# Fensterkontakt5.net
KiCad netlist of a schematic drawn in EAGLE
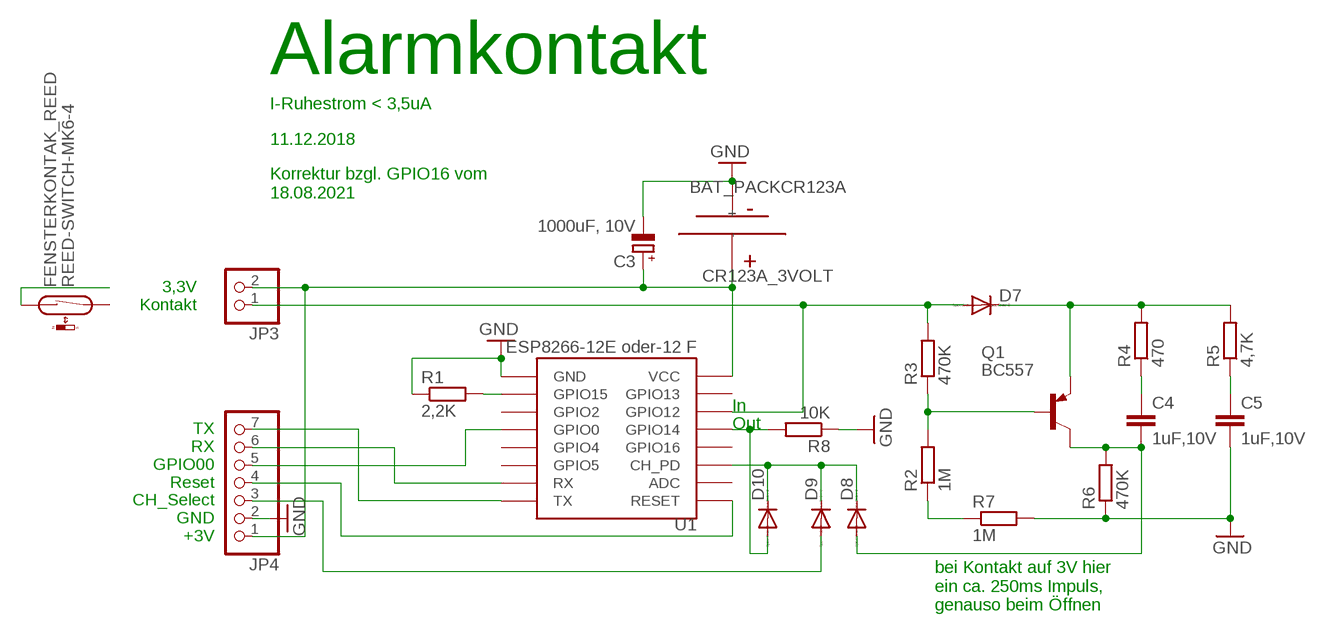
[diagram p0: schematic, sheet 1]

(export (version "E")
  (design (tool "Eeschema 10.0.6"))
  (components
    (comp (ref "C3")
      (value "1000uF, 10V")
      (footprint "eagle-import:E5-4")
      (libsource (lib "eagle-import") (part "CPOL-EUE5-4"))
    )
    (comp (ref "C4")
      (value "1uF,10V")
      (footprint "eagle-import:C075-032X103")
      (libsource (lib "eagle-import") (part "C-EU075-032X103"))
    )
    (comp (ref "C5")
      (value "1uF,10V")
      (footprint "eagle-import:C075-032X103")
      (libsource (lib "eagle-import") (part "C-EU075-032X103"))
    )
    (comp (ref "CR123A_3VOLT")
      (value "BAT_PACKCR123A")
      (footprint "eagle-import:BH123A")
      (fields (field (name "MANUFACTURER") "MPD") (field (name "MPN") "BH123A"))
      (libsource (lib "eagle-import") (part "BAT_PACKCR123A"))
    )
    (comp (ref "D7")
      (value "DIODE-D-7.5")
      (footprint "eagle-import:D-7.5")
      (libsource (lib "eagle-import") (part "DIODE-D-7.5"))
    )
    (comp (ref "D8")
      (value "DIODE-D-7.5")
      (footprint "eagle-import:D-7.5")
      (libsource (lib "eagle-import") (part "DIODE-D-7.5"))
    )
    (comp (ref "D9")
      (value "DIODE-D-7.5")
      (footprint "eagle-import:D-7.5")
      (libsource (lib "eagle-import") (part "DIODE-D-7.5"))
    )
    (comp (ref "D10")
      (value "DIODE-D-7.5")
      (footprint "eagle-import:D-7.5")
      (libsource (lib "eagle-import") (part "DIODE-D-7.5"))
    )
    (comp (ref "FENSTERKONTAK_REED")
      (value "REED-SWITCH-MK6-4")
      (footprint "eagle-import:MK6-4")
      (libsource (lib "eagle-import") (part "REED-SWITCH-MK6-4"))
    )
    (comp (ref "JP3")
      (value "PINHD-1X2")
      (footprint "eagle-import:1X02")
      (libsource (lib "eagle-import") (part "PINHD-1X2"))
    )
    (comp (ref "JP4")
      (value "PINHD-1X7")
      (footprint "eagle-import:1X07")
      (libsource (lib "eagle-import") (part "PINHD-1X7"))
    )
    (comp (ref "Q1")
      (value "BC557")
      (footprint "eagle-import:TO92-EBC")
      (libsource (lib "eagle-import") (part "BC557"))
    )
    (comp (ref "R1")
      (value "2,2K")
      (footprint "eagle-import:0207_7")
      (libsource (lib "eagle-import") (part "R-EU_0207/7"))
    )
    (comp (ref "R2")
      (value "1M")
      (footprint "eagle-import:0207_7")
      (libsource (lib "eagle-import") (part "R-EU_0207/7"))
    )
    (comp (ref "R3")
      (value "470K")
      (footprint "eagle-import:0207_7")
      (libsource (lib "eagle-import") (part "R-EU_0207/7"))
    )
    (comp (ref "R4")
      (value "470")
      (footprint "eagle-import:0207_7")
      (libsource (lib "eagle-import") (part "R-EU_0207/7"))
    )
    (comp (ref "R5")
      (value "4,7K")
      (footprint "eagle-import:0207_7")
      (libsource (lib "eagle-import") (part "R-EU_0207/7"))
    )
    (comp (ref "R6")
      (value "470K")
      (footprint "eagle-import:0207_7")
      (libsource (lib "eagle-import") (part "R-EU_0207/7"))
    )
    (comp (ref "R7")
      (value "1M")
      (footprint "eagle-import:0207_7")
      (libsource (lib "eagle-import") (part "R-EU_0207/7"))
    )
    (comp (ref "R8")
      (value "10K")
      (footprint "eagle-import:0207_7")
      (libsource (lib "eagle-import") (part "R-EU_0207/7"))
    )
    (comp (ref "U1")
      (value "ESP8266-12E oder-12 F")
      (footprint "eagle-import:ESP12")
      (libsource (lib "eagle-import") (part "ESP12"))
    )
  )
  (nets
    (net (code "1") (name "GND") (class "Default")
      (node (ref "C3") (pin "-") (pinfunction "-_-") (pintype "passive"))
      (node (ref "C5") (pin "2") (pinfunction "2_2") (pintype "passive"))
      (node (ref "CR123A_3VOLT") (pin "-") (pinfunction "-_-") (pintype "bidirectional"))
      (node (ref "JP4") (pin "2") (pinfunction "2_2") (pintype "passive"))
      (node (ref "R1") (pin "1") (pinfunction "1_1") (pintype "passive"))
      (node (ref "R6") (pin "1") (pinfunction "1_1") (pintype "passive"))
      (node (ref "R7") (pin "2") (pinfunction "2_2") (pintype "passive"))
      (node (ref "R8") (pin "1") (pinfunction "1_1") (pintype "passive"))
      (node (ref "U1") (pin "GND") (pinfunction "GND_GND") (pintype "bidirectional"))
    )
    (net (code "2") (name "Net-(C3-Pad+)") (class "Default")
      (node (ref "C3") (pin "+") (pinfunction "+_+") (pintype "passive"))
      (node (ref "CR123A_3VOLT") (pin "+") (pinfunction "+_+") (pintype "bidirectional"))
      (node (ref "JP3") (pin "2") (pinfunction "2_2") (pintype "passive"))
      (node (ref "JP4") (pin "1") (pinfunction "1_1") (pintype "passive"))
      (node (ref "U1") (pin "VCC") (pinfunction "VCC_VCC") (pintype "bidirectional"))
    )
    (net (code "3") (name "Net-(C4-Pad1)") (class "Default")
      (node (ref "C4") (pin "1") (pinfunction "1_1") (pintype "passive"))
      (node (ref "R4") (pin "1") (pinfunction "1_1") (pintype "passive"))
    )
    (net (code "4") (name "Net-(C4-Pad2)") (class "Default")
      (node (ref "C4") (pin "2") (pinfunction "2_2") (pintype "passive"))
      (node (ref "D8") (pin "A") (pinfunction "A_A") (pintype "passive"))
      (node (ref "Q1") (pin "C") (pinfunction "C_C") (pintype "passive"))
      (node (ref "R6") (pin "2") (pinfunction "2_2") (pintype "passive"))
    )
    (net (code "5") (name "Net-(C5-Pad1)") (class "Default")
      (node (ref "C5") (pin "1") (pinfunction "1_1") (pintype "passive"))
      (node (ref "R5") (pin "1") (pinfunction "1_1") (pintype "passive"))
    )
    (net (code "6") (name "Net-(D7-PadA)") (class "Default")
      (node (ref "D7") (pin "A") (pinfunction "A_A") (pintype "passive"))
      (node (ref "JP3") (pin "1") (pinfunction "1_1") (pintype "passive"))
      (node (ref "R3") (pin "2") (pinfunction "2_2") (pintype "passive"))
      (node (ref "U1") (pin "GPIO12") (pinfunction "GPIO12_GPIO12") (pintype "bidirectional"))
    )
    (net (code "7") (name "Net-(D7-PadC)") (class "Default")
      (node (ref "D7") (pin "C") (pinfunction "C_C") (pintype "passive"))
      (node (ref "Q1") (pin "E") (pinfunction "E_E") (pintype "passive"))
      (node (ref "R4") (pin "2") (pinfunction "2_2") (pintype "passive"))
      (node (ref "R5") (pin "2") (pinfunction "2_2") (pintype "passive"))
    )
    (net (code "8") (name "Net-(D9-PadA)") (class "Default")
      (node (ref "D9") (pin "A") (pinfunction "A_A") (pintype "passive"))
      (node (ref "JP4") (pin "3") (pinfunction "3_3") (pintype "passive"))
    )
    (net (code "9") (name "Net-(D10-PadA)") (class "Default")
      (node (ref "D10") (pin "A") (pinfunction "A_A") (pintype "passive"))
      (node (ref "R8") (pin "2") (pinfunction "2_2") (pintype "passive"))
      (node (ref "U1") (pin "GPIO14") (pinfunction "GPIO14_GPIO14") (pintype "bidirectional"))
    )
    (net (code "10") (name "Net-(D10-PadC)") (class "Default")
      (node (ref "D10") (pin "C") (pinfunction "C_C") (pintype "passive"))
      (node (ref "D8") (pin "C") (pinfunction "C_C") (pintype "passive"))
      (node (ref "D9") (pin "C") (pinfunction "C_C") (pintype "passive"))
      (node (ref "U1") (pin "CH_PD") (pinfunction "CH_PD_CH_PD") (pintype "bidirectional"))
    )
    (net (code "11") (name "Net-(JP4-Pad4)") (class "Default")
      (node (ref "JP4") (pin "4") (pinfunction "4_4") (pintype "passive"))
      (node (ref "U1") (pin "RESET") (pinfunction "RESET_RESET") (pintype "bidirectional"))
    )
    (net (code "12") (name "Net-(JP4-Pad5)") (class "Default")
      (node (ref "JP4") (pin "5") (pinfunction "5_5") (pintype "passive"))
      (node (ref "U1") (pin "GPIO0") (pinfunction "GPIO0_GPIO0") (pintype "bidirectional"))
    )
    (net (code "13") (name "Net-(JP4-Pad6)") (class "Default")
      (node (ref "JP4") (pin "6") (pinfunction "6_6") (pintype "passive"))
      (node (ref "U1") (pin "RX") (pinfunction "RX_RX") (pintype "bidirectional"))
    )
    (net (code "14") (name "Net-(JP4-Pad7)") (class "Default")
      (node (ref "JP4") (pin "7") (pinfunction "7_7") (pintype "passive"))
      (node (ref "U1") (pin "TX") (pinfunction "TX_TX") (pintype "bidirectional"))
    )
    (net (code "15") (name "Net-(Q1-PadB)") (class "Default")
      (node (ref "Q1") (pin "B") (pinfunction "B_B") (pintype "passive"))
      (node (ref "R2") (pin "2") (pinfunction "2_2") (pintype "passive"))
      (node (ref "R3") (pin "1") (pinfunction "1_1") (pintype "passive"))
    )
    (net (code "16") (name "Net-(R1-Pad2)") (class "Default")
      (node (ref "R1") (pin "2") (pinfunction "2_2") (pintype "passive"))
      (node (ref "U1") (pin "GPIO15") (pinfunction "GPIO15_GPIO15") (pintype "bidirectional"))
    )
    (net (code "17") (name "Net-(R2-Pad1)") (class "Default")
      (node (ref "R2") (pin "1") (pinfunction "1_1") (pintype "passive"))
      (node (ref "R7") (pin "1") (pinfunction "1_1") (pintype "passive"))
    )
    (net (code "18") (name "unconnected-(FENSTERKONTAK_REED-Pad1)") (class "Default")
      (node (ref "FENSTERKONTAK_REED") (pin "1") (pinfunction "1_1") (pintype "passive"))
    )
    (net (code "19") (name "unconnected-(FENSTERKONTAK_REED-Pad2)") (class "Default")
      (node (ref "FENSTERKONTAK_REED") (pin "2") (pinfunction "2_2") (pintype "passive"))
    )
    (net (code "20") (name "unconnected-(U1-PadADC)") (class "Default")
      (node (ref "U1") (pin "ADC") (pinfunction "ADC_ADC") (pintype "bidirectional"))
    )
    (net (code "21") (name "unconnected-(U1-PadGPIO2)") (class "Default")
      (node (ref "U1") (pin "GPIO2") (pinfunction "GPIO2_GPIO2") (pintype "bidirectional"))
    )
    (net (code "22") (name "unconnected-(U1-PadGPIO4)") (class "Default")
      (node (ref "U1") (pin "GPIO4") (pinfunction "GPIO4_GPIO4") (pintype "bidirectional"))
    )
    (net (code "23") (name "unconnected-(U1-PadGPIO5)") (class "Default")
      (node (ref "U1") (pin "GPIO5") (pinfunction "GPIO5_GPIO5") (pintype "bidirectional"))
    )
    (net (code "24") (name "unconnected-(U1-PadGPIO13)") (class "Default")
      (node (ref "U1") (pin "GPIO13") (pinfunction "GPIO13_GPIO13") (pintype "bidirectional"))
    )
    (net (code "25") (name "unconnected-(U1-PadGPIO16)") (class "Default")
      (node (ref "U1") (pin "GPIO16") (pinfunction "GPIO16_GPIO16") (pintype "bidirectional"))
    )
  )
)
